# CON_MINI_USBB_RA.net
KiCad netlist of a schematic drawn in Altium Designer
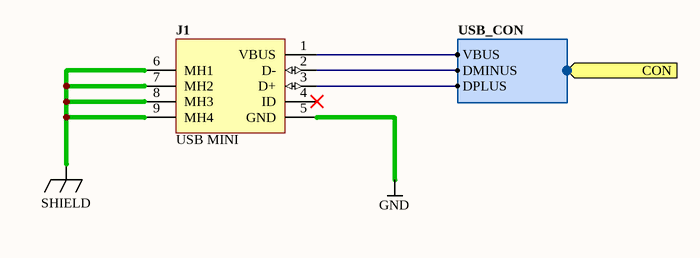
[diagram p0: CON_MINI_USBB_RA.SchDoc]

(export (version "E")
  (design (tool "Eeschema 10.0.6"))
  (components
    (comp (ref "J1")
      (value "USB MINI")
      (footprint "USB-MOLEX-675031020")
      (description "USB, MINI, SMD,  Molex")
      (libsource (lib "AltiumDesignLibrary") (part "048190-0001"))
    )
  )
  (nets
    (net (code "2") (name "/DMINUS") (class "Default")
      (node (ref "J1") (pin "2") (pinfunction "D-_2") (pintype "bidirectional"))
    )
    (net (code "3") (name "/DPLUS") (class "Default")
      (node (ref "J1") (pin "3") (pinfunction "D+_3") (pintype "bidirectional"))
    )
    (net (code "4") (name "/VBUS") (class "Default")
      (node (ref "J1") (pin "1") (pinfunction "VBUS_1") (pintype "power_in"))
    )
    (net (code "6") (name "GND") (class "Default")
      (node (ref "J1") (pin "5") (pinfunction "GND_5") (pintype "power_in"))
    )
    (net (code "7") (name "SHIELD") (class "Default")
      (node (ref "J1") (pin "6") (pinfunction "MH1_6") (pintype "passive"))
      (node (ref "J1") (pin "7") (pinfunction "MH2_7") (pintype "passive"))
      (node (ref "J1") (pin "8") (pinfunction "MH3_8") (pintype "passive"))
      (node (ref "J1") (pin "9") (pinfunction "MH4_9") (pintype "passive"))
    )
    (net (code "8") (name "unconnected-(J1-ID-Pad4)") (class "Default")
      (node (ref "J1") (pin "4") (pinfunction "ID_4") (pintype "passive+no_connect"))
    )
  )
)
